# Bottom.net
KiCad netlist of a schematic drawn in EAGLE
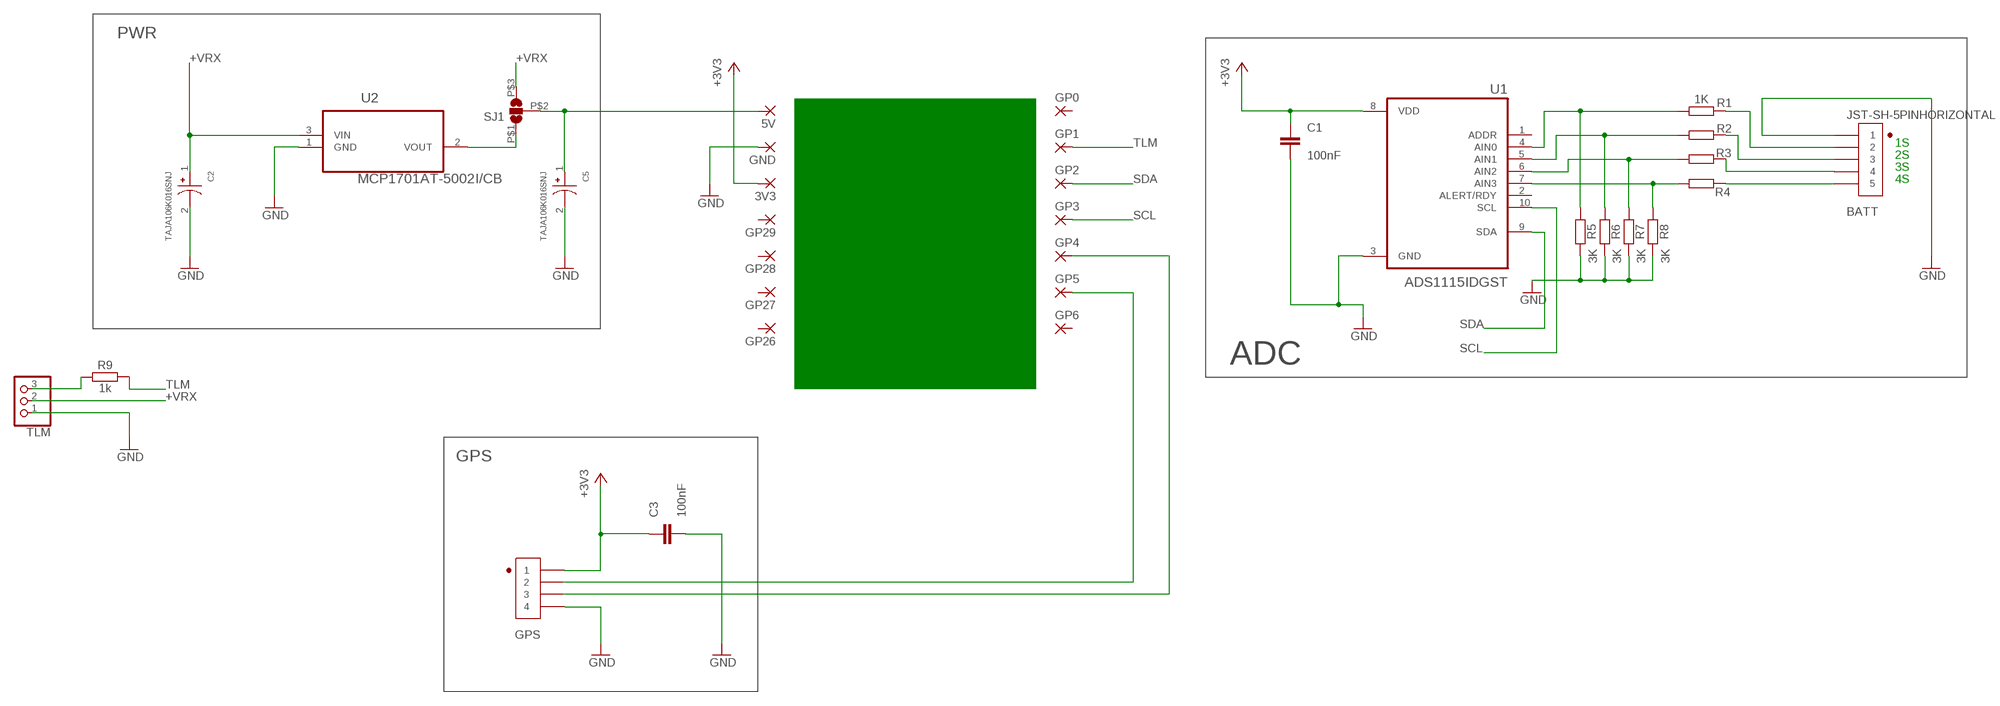
[diagram p0: schematic, sheet 1]

(export (version "E")
  (design (tool "Eeschema 10.0.6"))
  (components
    (comp (ref "3V3")
      (value "1,6/0,9")
      (footprint "eagle-import:1,6_0,9")
      (libsource (lib "eagle-import") (part "1,6/0,9"))
    )
    (comp (ref "5V")
      (value "1,6/0,9")
      (footprint "eagle-import:1,6_0,9")
      (libsource (lib "eagle-import") (part "1,6/0,9"))
    )
    (comp (ref "BATT")
      (value "JST-SH-5PINHORIZONTAL")
      (footprint "eagle-import:JST-SH-5PIN-1.0MM")
      (libsource (lib "eagle-import") (part "JST-SH-5PINHORIZONTAL"))
    )
    (comp (ref "C1")
      (value "100nF")
      (footprint "eagle-import:0603")
      (libsource (lib "eagle-import") (part "1.0UF-0603-16V-10%-X7R"))
    )
    (comp (ref "C2")
      (value "TAJA106K016SNJ")
      (footprint "eagle-import:CAPMP3216X180N")
      (fields (field (name "MF") "AVX"))
      (libsource (lib "eagle-import") (part "TAJA106K016SNJ"))
    )
    (comp (ref "C3")
      (value "100nF")
      (footprint "eagle-import:0603")
      (libsource (lib "eagle-import") (part "1.0UF-0603-16V-10%-X7R"))
    )
    (comp (ref "C5")
      (value "TAJA106K016SNJ")
      (footprint "eagle-import:CAPMP3216X180N")
      (fields (field (name "MF") "AVX"))
      (libsource (lib "eagle-import") (part "TAJA106K016SNJ"))
    )
    (comp (ref "GND")
      (value "1,6/0,9")
      (footprint "eagle-import:1,6_0,9")
      (libsource (lib "eagle-import") (part "1,6/0,9"))
    )
    (comp (ref "GP0")
      (value "1,6/0,9")
      (footprint "eagle-import:1,6_0,9")
      (libsource (lib "eagle-import") (part "1,6/0,9"))
    )
    (comp (ref "GP1")
      (value "1,6/0,9")
      (footprint "eagle-import:1,6_0,9")
      (libsource (lib "eagle-import") (part "1,6/0,9"))
    )
    (comp (ref "GP2")
      (value "1,6/0,9")
      (footprint "eagle-import:1,6_0,9")
      (libsource (lib "eagle-import") (part "1,6/0,9"))
    )
    (comp (ref "GP3")
      (value "1,6/0,9")
      (footprint "eagle-import:1,6_0,9")
      (libsource (lib "eagle-import") (part "1,6/0,9"))
    )
    (comp (ref "GP4")
      (value "1,6/0,9")
      (footprint "eagle-import:1,6_0,9")
      (libsource (lib "eagle-import") (part "1,6/0,9"))
    )
    (comp (ref "GP5")
      (value "1,6/0,9")
      (footprint "eagle-import:1,6_0,9")
      (libsource (lib "eagle-import") (part "1,6/0,9"))
    )
    (comp (ref "GP6")
      (value "1,6/0,9")
      (footprint "eagle-import:1,6_0,9")
      (libsource (lib "eagle-import") (part "1,6/0,9"))
    )
    (comp (ref "GP26")
      (value "1,6/0,9")
      (footprint "eagle-import:1,6_0,9")
      (libsource (lib "eagle-import") (part "1,6/0,9"))
    )
    (comp (ref "GP27")
      (value "1,6/0,9")
      (footprint "eagle-import:1,6_0,9")
      (libsource (lib "eagle-import") (part "1,6/0,9"))
    )
    (comp (ref "GP28")
      (value "1,6/0,9")
      (footprint "eagle-import:1,6_0,9")
      (libsource (lib "eagle-import") (part "1,6/0,9"))
    )
    (comp (ref "GP29")
      (value "1,6/0,9")
      (footprint "eagle-import:1,6_0,9")
      (libsource (lib "eagle-import") (part "1,6/0,9"))
    )
    (comp (ref "GPS")
      (value "JST-SH-4PINJST-SH-4-HORIZONTAL")
      (footprint "eagle-import:JST-SH-4PIN-1.0MM")
      (libsource (lib "eagle-import") (part "JST-SH-4PINJST-SH-4-HORIZONTAL"))
    )
    (comp (ref "R1")
      (value "1K")
      (footprint "eagle-import:0603")
      (libsource (lib "eagle-import") (part "RESISTOR0603"))
    )
    (comp (ref "R2")
      (value "RESISTOR0603")
      (footprint "eagle-import:0603")
      (libsource (lib "eagle-import") (part "RESISTOR0603"))
    )
    (comp (ref "R3")
      (value "RESISTOR0603")
      (footprint "eagle-import:0603")
      (libsource (lib "eagle-import") (part "RESISTOR0603"))
    )
    (comp (ref "R4")
      (value "RESISTOR0603")
      (footprint "eagle-import:0603")
      (libsource (lib "eagle-import") (part "RESISTOR0603"))
    )
    (comp (ref "R5")
      (value "3K")
      (footprint "eagle-import:0603")
      (libsource (lib "eagle-import") (part "RESISTOR0603"))
    )
    (comp (ref "R6")
      (value "3K")
      (footprint "eagle-import:0603")
      (libsource (lib "eagle-import") (part "RESISTOR0603"))
    )
    (comp (ref "R7")
      (value "3K")
      (footprint "eagle-import:0603")
      (libsource (lib "eagle-import") (part "RESISTOR0603"))
    )
    (comp (ref "R8")
      (value "3K")
      (footprint "eagle-import:0603")
      (libsource (lib "eagle-import") (part "RESISTOR0603"))
    )
    (comp (ref "R9")
      (value "1k")
      (footprint "eagle-import:0603")
      (libsource (lib "eagle-import") (part "RESISTOR0603"))
    )
    (comp (ref "SJ1")
      (value "SJ2WSJ_TINY")
      (footprint "eagle-import:SJ_TINY")
      (libsource (lib "eagle-import") (part "SJ2WSJ_TINY"))
    )
    (comp (ref "TLM")
      (value "PINHD-1X390")
      (footprint "eagle-import:1X03-ANGLE")
      (libsource (lib "eagle-import") (part "PINHD-1X390"))
    )
    (comp (ref "U1")
      (value "ADS1115IDGST")
      (footprint "eagle-import:SOP50P490X110-10N")
      (fields (field (name "MF") "Texas Instruments"))
      (libsource (lib "eagle-import") (part "ADS1115IDGST"))
    )
    (comp (ref "U2")
      (value "MCP1701AT-5002I/CB")
      (footprint "eagle-import:SOT95P255X145-3N")
      (fields (field (name "MF") "Microchip"))
      (libsource (lib "eagle-import") (part "MCP1701AT-5002I/CB"))
    )
  )
  (nets
    (net (code "1") (name "+3V3") (class "Default")
      (node (ref "3V3") (pin "1") (pinfunction "P_1") (pintype "passive"))
      (node (ref "C1") (pin "1") (pinfunction "1_1") (pintype "passive"))
      (node (ref "C3") (pin "1") (pinfunction "1_1") (pintype "passive"))
      (node (ref "GPS") (pin "1") (pinfunction "1_1") (pintype "bidirectional"))
      (node (ref "U1") (pin "8") (pinfunction "VDD_8") (pintype "power_in"))
    )
    (net (code "2") (name "/+VRX") (class "Default")
      (node (ref "C2") (pin "1") (pinfunction "1_1") (pintype "passive"))
      (node (ref "SJ1") (pin "P$3") (pinfunction "3_P$3") (pintype "passive"))
      (node (ref "TLM") (pin "2") (pinfunction "2_2") (pintype "passive"))
      (node (ref "U2") (pin "3") (pinfunction "VIN_3") (pintype "input"))
    )
    (net (code "3") (name "/SCL") (class "Default")
      (node (ref "GP3") (pin "1") (pinfunction "P_1") (pintype "passive"))
      (node (ref "U1") (pin "10") (pinfunction "SCL_10") (pintype "input"))
    )
    (net (code "4") (name "/SDA") (class "Default")
      (node (ref "GP2") (pin "1") (pinfunction "P_1") (pintype "passive"))
      (node (ref "U1") (pin "9") (pinfunction "SDA_9") (pintype "bidirectional"))
    )
    (net (code "5") (name "/TLM") (class "Default")
      (node (ref "GP1") (pin "1") (pinfunction "P_1") (pintype "passive"))
      (node (ref "R9") (pin "2") (pinfunction "2_2") (pintype "passive"))
    )
    (net (code "6") (name "GND") (class "Default")
      (node (ref "BATT") (pin "1") (pinfunction "1_1") (pintype "bidirectional"))
      (node (ref "C1") (pin "2") (pinfunction "2_2") (pintype "passive"))
      (node (ref "C2") (pin "2") (pinfunction "2_2") (pintype "passive"))
      (node (ref "C3") (pin "2") (pinfunction "2_2") (pintype "passive"))
      (node (ref "C5") (pin "2") (pinfunction "2_2") (pintype "passive"))
      (node (ref "GND") (pin "1") (pinfunction "P_1") (pintype "passive"))
      (node (ref "GPS") (pin "4") (pinfunction "4_4") (pintype "bidirectional"))
      (node (ref "R5") (pin "2") (pinfunction "2_2") (pintype "passive"))
      (node (ref "R6") (pin "2") (pinfunction "2_2") (pintype "passive"))
      (node (ref "R7") (pin "2") (pinfunction "2_2") (pintype "passive"))
      (node (ref "R8") (pin "2") (pinfunction "2_2") (pintype "passive"))
      (node (ref "TLM") (pin "1") (pinfunction "1_1") (pintype "passive"))
      (node (ref "U1") (pin "3") (pinfunction "GND_3") (pintype "power_in"))
      (node (ref "U2") (pin "1") (pinfunction "GND_1") (pintype "passive"))
    )
    (net (code "7") (name "Net-(5V-P)") (class "Default")
      (node (ref "5V") (pin "1") (pinfunction "P_1") (pintype "passive"))
      (node (ref "C5") (pin "1") (pinfunction "1_1") (pintype "passive"))
      (node (ref "SJ1") (pin "P$2") (pinfunction "2_P$2") (pintype "passive"))
    )
    (net (code "8") (name "Net-(BATT-Pad2)") (class "Default")
      (node (ref "BATT") (pin "2") (pinfunction "2_2") (pintype "bidirectional"))
      (node (ref "R1") (pin "1") (pinfunction "1_1") (pintype "passive"))
    )
    (net (code "9") (name "Net-(BATT-Pad3)") (class "Default")
      (node (ref "BATT") (pin "3") (pinfunction "3_3") (pintype "bidirectional"))
      (node (ref "R2") (pin "1") (pinfunction "1_1") (pintype "passive"))
    )
    (net (code "10") (name "Net-(BATT-Pad4)") (class "Default")
      (node (ref "BATT") (pin "4") (pinfunction "4_4") (pintype "bidirectional"))
      (node (ref "R3") (pin "1") (pinfunction "1_1") (pintype "passive"))
    )
    (net (code "11") (name "Net-(BATT-Pad5)") (class "Default")
      (node (ref "BATT") (pin "5") (pinfunction "5_5") (pintype "bidirectional"))
      (node (ref "R4") (pin "1") (pinfunction "1_1") (pintype "passive"))
    )
    (net (code "12") (name "Net-(GP4-P)") (class "Default")
      (node (ref "GP4") (pin "1") (pinfunction "P_1") (pintype "passive"))
      (node (ref "GPS") (pin "3") (pinfunction "3_3") (pintype "bidirectional"))
    )
    (net (code "13") (name "Net-(GP5-P)") (class "Default")
      (node (ref "GP5") (pin "1") (pinfunction "P_1") (pintype "passive"))
      (node (ref "GPS") (pin "2") (pinfunction "2_2") (pintype "bidirectional"))
    )
    (net (code "14") (name "Net-(R9-Pad1)") (class "Default")
      (node (ref "R9") (pin "1") (pinfunction "1_1") (pintype "passive"))
      (node (ref "TLM") (pin "3") (pinfunction "3_3") (pintype "passive"))
    )
    (net (code "15") (name "Net-(SJ1-1)") (class "Default")
      (node (ref "SJ1") (pin "P$1") (pinfunction "1_P$1") (pintype "passive"))
      (node (ref "U2") (pin "2") (pinfunction "VOUT_2") (pintype "output"))
    )
    (net (code "16") (name "Net-(U1-AIN0)") (class "Default")
      (node (ref "R1") (pin "2") (pinfunction "2_2") (pintype "passive"))
      (node (ref "R5") (pin "1") (pinfunction "1_1") (pintype "passive"))
      (node (ref "U1") (pin "4") (pinfunction "AIN0_4") (pintype "input"))
    )
    (net (code "17") (name "Net-(U1-AIN1)") (class "Default")
      (node (ref "R2") (pin "2") (pinfunction "2_2") (pintype "passive"))
      (node (ref "R6") (pin "1") (pinfunction "1_1") (pintype "passive"))
      (node (ref "U1") (pin "5") (pinfunction "AIN1_5") (pintype "input"))
    )
    (net (code "18") (name "Net-(U1-AIN2)") (class "Default")
      (node (ref "R3") (pin "2") (pinfunction "2_2") (pintype "passive"))
      (node (ref "R7") (pin "1") (pinfunction "1_1") (pintype "passive"))
      (node (ref "U1") (pin "6") (pinfunction "AIN2_6") (pintype "input"))
    )
    (net (code "19") (name "Net-(U1-AIN3)") (class "Default")
      (node (ref "R4") (pin "2") (pinfunction "2_2") (pintype "passive"))
      (node (ref "R8") (pin "1") (pinfunction "1_1") (pintype "passive"))
      (node (ref "U1") (pin "7") (pinfunction "AIN3_7") (pintype "input"))
    )
    (net (code "20") (name "unconnected-(GP0-P-Pad1)") (class "Default")
      (node (ref "GP0") (pin "1") (pinfunction "P_1") (pintype "passive"))
    )
    (net (code "21") (name "unconnected-(GP6-P-Pad1)") (class "Default")
      (node (ref "GP6") (pin "1") (pinfunction "P_1") (pintype "passive"))
    )
    (net (code "22") (name "unconnected-(GP26-P-Pad1)") (class "Default")
      (node (ref "GP26") (pin "1") (pinfunction "P_1") (pintype "passive"))
    )
    (net (code "23") (name "unconnected-(GP27-P-Pad1)") (class "Default")
      (node (ref "GP27") (pin "1") (pinfunction "P_1") (pintype "passive"))
    )
    (net (code "24") (name "unconnected-(GP28-P-Pad1)") (class "Default")
      (node (ref "GP28") (pin "1") (pinfunction "P_1") (pintype "passive"))
    )
    (net (code "25") (name "unconnected-(GP29-P-Pad1)") (class "Default")
      (node (ref "GP29") (pin "1") (pinfunction "P_1") (pintype "passive"))
    )
    (net (code "26") (name "unconnected-(U1-ADDR-Pad1)") (class "Default")
      (node (ref "U1") (pin "1") (pinfunction "ADDR_1") (pintype "input"))
    )
    (net (code "27") (name "unconnected-(U1-ALERT{slash}RDY-Pad2)") (class "Default")
      (node (ref "U1") (pin "2") (pinfunction "ALERT/RDY_2") (pintype "input"))
    )
  )
)
